# DC-DC_Regulator.net
KiCad netlist of a schematic drawn in Altium Designer
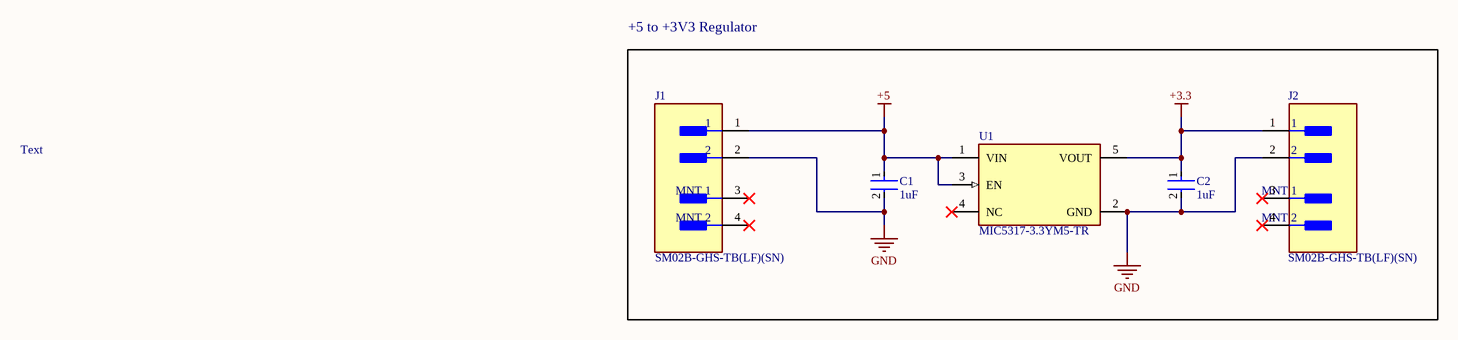
[diagram p0: DC-DC_Regulator.SchDoc]

(export (version "E")
  (design (tool "Eeschema 10.0.6"))
  (components
    (comp (ref "C1")
      (value "1uF")
      (footprint "FP-CC0805-0_85-MFG")
      (description "CAP CER 1UF 10V X7R 0805")
      (fields
        (field (name "MANUFACTURER") "Yageo")
        (field (name "OCTOPART") "https://octopart.com/cc0805kkx7r6bb105-yageo-42522859")
      )
      (libsource (lib "Altium Content Vault") (part "11868f565c42a9108669ba33697ecf6"))
    )
    (comp (ref "C2")
      (value "1uF")
      (footprint "FP-CC0805-0_85-MFG")
      (description "CAP CER 1UF 10V X7R 0805")
      (fields
        (field (name "MANUFACTURER") "Yageo")
        (field (name "OCTOPART") "https://octopart.com/cc0805kkx7r6bb105-yageo-42522859")
      )
      (libsource (lib "Altium Content Vault") (part "11868f565c42a9108669ba33697ecf6"))
    )
    (comp (ref "J1")
      (value "SM02B-GHS-TB(LF)(SN)")
      (footprint "FP-SM02B-GHS-TB_LF_SN-MFG")
      (description "CONN HEADER SMD R/A 2POS 1.25MM")
      (libsource (lib "Altium Content Vault") (part "56ec3178a87b3978bdc1b3682cd516a"))
    )
    (comp (ref "J2")
      (value "SM02B-GHS-TB(LF)(SN)")
      (footprint "FP-SM02B-GHS-TB_LF_SN-MFG")
      (description "CONN HEADER SMD R/A 2POS 1.25MM")
      (libsource (lib "") (part "56ec3178a87b3978bdc1b3682cd516a_1"))
    )
    (comp (ref "U1")
      (value "MIC5317-3.3YM5-TR")
      (footprint "FP-SOT23-5LD-PL-1-MFG")
      (description "IC REG LINEAR 3.3V 150MA SOT23-5")
      (libsource (lib "Altium Content Vault") (part "0a093dae7315cdc977fd108dde87457"))
    )
  )
  (nets
    (net (code "1") (name "+3.3") (class "Default")
      (node (ref "C2") (pin "1") (pinfunction "1_1") (pintype "passive"))
      (node (ref "J2") (pin "1") (pinfunction "1_1") (pintype "passive"))
      (node (ref "U1") (pin "5") (pinfunction "VOUT_5") (pintype "power_in"))
    )
    (net (code "2") (name "+5") (class "Default")
      (node (ref "C1") (pin "1") (pinfunction "1_1") (pintype "passive"))
      (node (ref "J1") (pin "1") (pinfunction "1_1") (pintype "passive"))
      (node (ref "U1") (pin "1") (pinfunction "VIN_1") (pintype "power_in"))
      (node (ref "U1") (pin "3") (pinfunction "EN_3") (pintype "input"))
    )
    (net (code "3") (name "GND") (class "Default")
      (node (ref "C1") (pin "2") (pinfunction "2_2") (pintype "passive"))
      (node (ref "C2") (pin "2") (pinfunction "2_2") (pintype "passive"))
      (node (ref "J1") (pin "2") (pinfunction "2_2") (pintype "passive"))
      (node (ref "J2") (pin "2") (pinfunction "2_2") (pintype "passive"))
      (node (ref "U1") (pin "2") (pinfunction "GND_2") (pintype "power_in"))
    )
    (net (code "4") (name "unconnected-(J1-MNT_1-Pad3)") (class "Default")
      (node (ref "J1") (pin "3") (pinfunction "MNT_1_3") (pintype "passive+no_connect"))
    )
    (net (code "5") (name "unconnected-(J1-MNT_2-Pad4)") (class "Default")
      (node (ref "J1") (pin "4") (pinfunction "MNT_2_4") (pintype "passive+no_connect"))
    )
    (net (code "6") (name "unconnected-(J2-MNT_1-Pad3)") (class "Default")
      (node (ref "J2") (pin "3") (pinfunction "MNT_1_3") (pintype "passive+no_connect"))
    )
    (net (code "7") (name "unconnected-(J2-MNT_2-Pad4)") (class "Default")
      (node (ref "J2") (pin "4") (pinfunction "MNT_2_4") (pintype "passive+no_connect"))
    )
    (net (code "8") (name "unconnected-(U1-NC-Pad4)") (class "Default")
      (node (ref "U1") (pin "4") (pinfunction "NC_4") (pintype "passive+no_connect"))
    )
  )
)
